# supply.net
KiCad netlist of a schematic drawn in Altium Designer
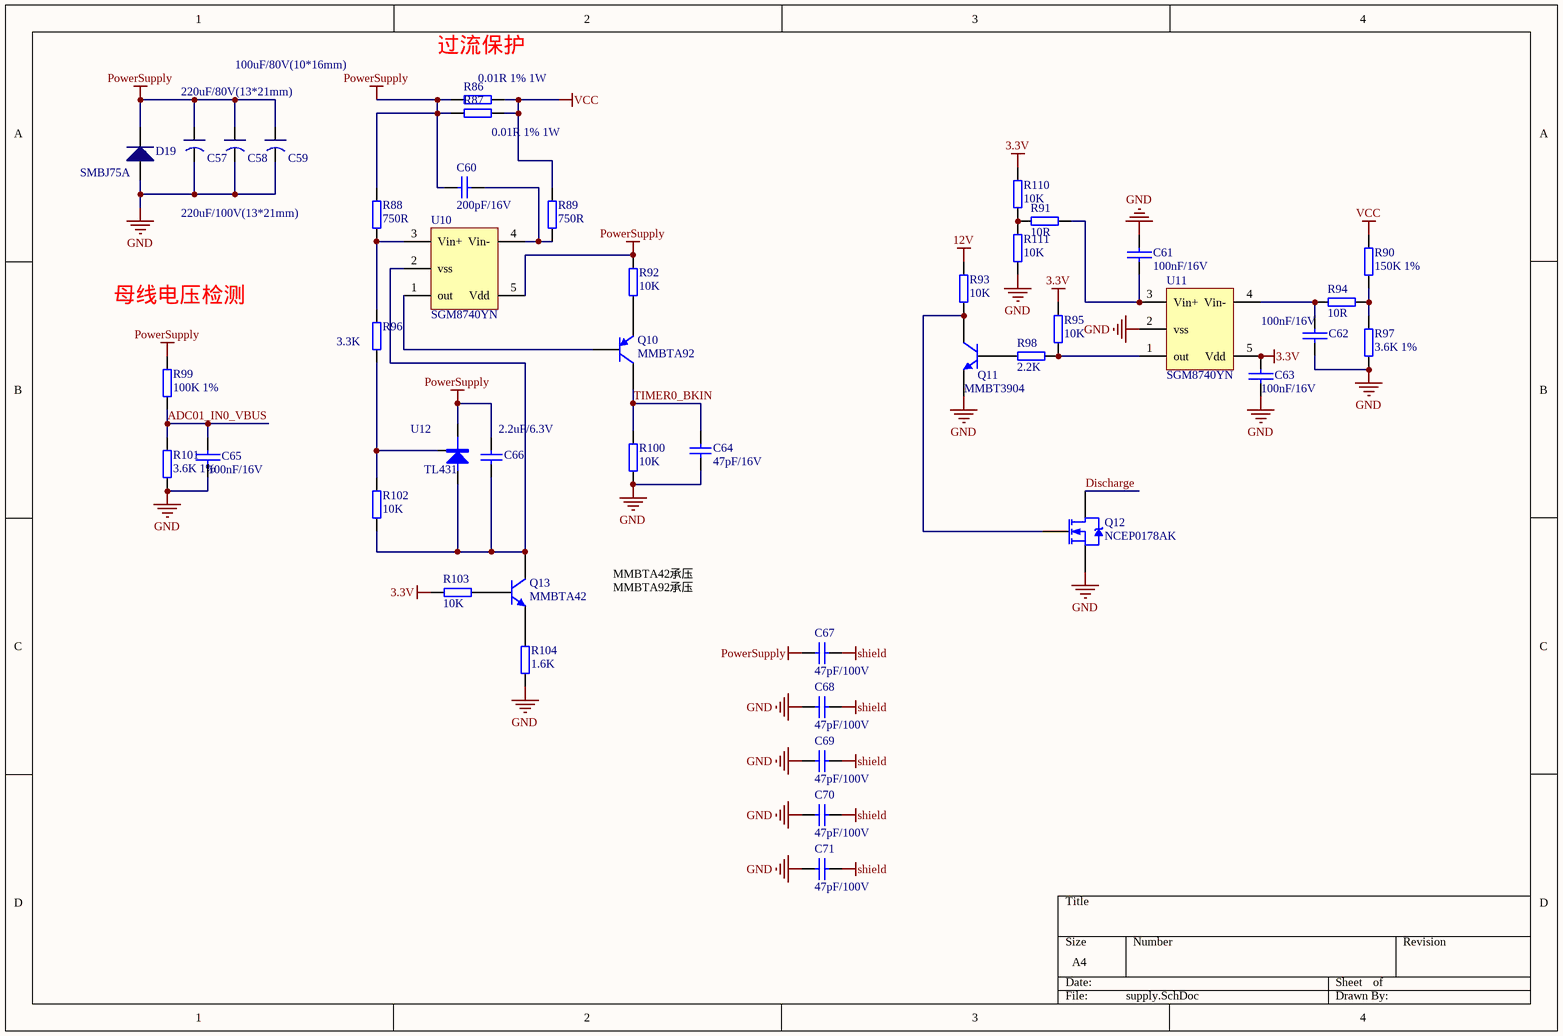
[diagram p0: supply.SchDoc]

(export (version "E")
  (design (tool "Eeschema 10.0.6"))
  (components
    (comp (ref "C57")
      (value "220uF/80V(13*21mm)")
      (footprint "AL-ELEC 13*21mm")
      (description "铝电解电容")
      (libsource (lib "Common Device") (part "Capacitor"))
    )
    (comp (ref "C58")
      (value "220uF/100V(13*21mm)")
      (footprint "AL-ELEC 13*21mm")
      (description "铝电解电容")
      (libsource (lib "Common Device") (part "Capacitor"))
    )
    (comp (ref "C59")
      (value "100uF/80V(10*16mm)")
      (footprint "AL-ELEC 10*16mm")
      (description "铝电解电容")
      (libsource (lib "Common Device") (part "Capacitor"))
    )
    (comp (ref "C60") (value "200pF/16V") (footprint "C0402") (libsource (lib "zijianku") (part "cap")))
    (comp (ref "C61")
      (value "100nF/16V")
      (footprint "C0402")
      (description "Capacitor")
      (libsource (lib "*") (part "CAP"))
    )
    (comp (ref "C62")
      (value "100nF/16V")
      (footprint "C0402")
      (description "Capacitor")
      (libsource (lib "*") (part "CAP"))
    )
    (comp (ref "C63")
      (value "100nF/16V")
      (footprint "C0402")
      (description "Capacitor")
      (libsource (lib "*") (part "CAP"))
    )
    (comp (ref "C64") (value "47pF/16V") (footprint "C0402") (libsource (lib "zijianku") (part "cap")))
    (comp (ref "C65")
      (value "100nF/16V")
      (footprint "C0402")
      (description "Capacitor")
      (libsource (lib "*") (part "CAP"))
    )
    (comp (ref "C66") (value "2.2uF/6.3V") (footprint "C0402") (libsource (lib "zijianku") (part "cap")))
    (comp (ref "C67") (value "47pF/100V") (footprint "C1206") (libsource (lib "zijianku") (part "cap")))
    (comp (ref "C68") (value "47pF/100V") (footprint "C1206") (libsource (lib "zijianku") (part "cap")))
    (comp (ref "C69") (value "47pF/100V") (footprint "C1206") (libsource (lib "zijianku") (part "cap")))
    (comp (ref "C70") (value "47pF/100V") (footprint "C1206") (libsource (lib "zijianku") (part "cap")))
    (comp (ref "C71") (value "47pF/100V") (footprint "C1206") (libsource (lib "zijianku") (part "cap")))
    (comp (ref "D19")
      (value "SMBJ75A")
      (footprint "DO-214AA SMB")
      (libsource (lib "Common Device") (part "Diode"))
    )
    (comp (ref "Q10") (value "MMBTA92") (footprint "SOT-23") (libsource (lib "zijianku") (part "PNP")))
    (comp (ref "Q11") (value "MMBT3904") (footprint "SOT-23") (libsource (lib "zijianku") (part "NPN")))
    (comp (ref "Q12")
      (value "NCEP0178AK")
      (footprint "D-PAK(TO-252AA)")
      (libsource (lib "zijianku") (part "N-channel Enhancement MOS"))
    )
    (comp (ref "Q13") (value "MMBTA42") (footprint "SOT-23") (libsource (lib "zijianku") (part "NPN")))
    (comp (ref "R86")
      (value "0.01R 1% 1W")
      (footprint "R1210")
      (libsource (lib "zijianku") (part "Resistance"))
    )
    (comp (ref "R87")
      (value "0.01R 1% 1W")
      (footprint "R1210")
      (libsource (lib "zijianku") (part "Resistance"))
    )
    (comp (ref "R88") (value "750R") (footprint "R0402") (libsource (lib "zijianku") (part "Resistance")))
    (comp (ref "R89") (value "750R") (footprint "R0402") (libsource (lib "zijianku") (part "Resistance")))
    (comp (ref "R90") (value "150K 1%") (footprint "R0603") (libsource (lib "zijianku") (part "Resistance")))
    (comp (ref "R91") (value "10R") (footprint "R0402") (libsource (lib "zijianku") (part "Resistance")))
    (comp (ref "R92") (value "10K") (footprint "R0402") (libsource (lib "zijianku") (part "Resistance")))
    (comp (ref "R93") (value "10K") (footprint "R0402") (libsource (lib "zijianku") (part "Resistance")))
    (comp (ref "R94") (value "10R") (footprint "R0402") (libsource (lib "zijianku") (part "Resistance")))
    (comp (ref "R95") (value "10K") (footprint "R0402") (libsource (lib "zijianku") (part "Resistance")))
    (comp (ref "R96") (value "3.3K") (footprint "R0402") (libsource (lib "zijianku") (part "Resistance")))
    (comp (ref "R97") (value "3.6K 1%") (footprint "R0603") (libsource (lib "zijianku") (part "Resistance")))
    (comp (ref "R98") (value "2.2K") (footprint "R0402") (libsource (lib "zijianku") (part "Resistance")))
    (comp (ref "R99") (value "100K 1%") (footprint "R0603") (libsource (lib "zijianku") (part "Resistance")))
    (comp (ref "R100") (value "10K") (footprint "R0402") (libsource (lib "zijianku") (part "Resistance")))
    (comp (ref "R101") (value "3.6K 1%") (footprint "R0603") (libsource (lib "zijianku") (part "Resistance")))
    (comp (ref "R102") (value "10K") (footprint "R0402") (libsource (lib "zijianku") (part "Resistance")))
    (comp (ref "R103") (value "10K") (footprint "R0402") (libsource (lib "zijianku") (part "Resistance")))
    (comp (ref "R104") (value "1.6K") (footprint "R0402") (libsource (lib "zijianku") (part "Resistance")))
    (comp (ref "R110") (value "10K") (footprint "R0402") (libsource (lib "zijianku") (part "Resistance")))
    (comp (ref "R111") (value "10K") (footprint "R0402") (libsource (lib "zijianku") (part "Resistance")))
    (comp (ref "U10")
      (value "SGM8740YN")
      (footprint "SOT-23(5)")
      (description "圣邦微电子 丝印 SL5XX")
      (libsource (lib "Common Device") (part "LMV7239"))
    )
    (comp (ref "U11")
      (value "SGM8740YN")
      (footprint "SOT-23(5)")
      (description "圣邦微电子 丝印 SL5XX")
      (libsource (lib "Common Device") (part "LMV7239"))
    )
    (comp (ref "U12")
      (value "TL431")
      (footprint "SOT-23")
      (description "注意引脚关系：1-C 2-R 3-A")
      (libsource (lib "zijianku") (part "TL431A"))
    )
  )
  (nets
    (net (code "1") (name "/ADC01_IN0_VBUS") (class "Default")
      (node (ref "C65") (pin "1") (pinfunction "1_1") (pintype "passive"))
      (node (ref "R101") (pin "2") (pintype "passive"))
      (node (ref "R99") (pin "1") (pintype "passive"))
    )
    (net (code "2") (name "/Discharge") (class "Default")
      (node (ref "Q12") (pin "3") (pinfunction "D_3") (pintype "passive"))
    )
    (net (code "3") (name "/TIMER0_BKIN") (class "Default")
      (node (ref "C64") (pin "1") (pinfunction "0_1") (pintype "passive"))
      (node (ref "Q10") (pin "3") (pinfunction "C_3") (pintype "passive"))
      (node (ref "R100") (pin "2") (pintype "passive"))
    )
    (net (code "4") (name "3.3V") (class "Default")
      (node (ref "C63") (pin "1") (pinfunction "1_1") (pintype "passive"))
      (node (ref "R103") (pin "1") (pintype "passive"))
      (node (ref "R110") (pin "2") (pintype "passive"))
      (node (ref "R95") (pin "2") (pintype "passive"))
      (node (ref "U11") (pin "5") (pinfunction "Vdd_5") (pintype "passive"))
    )
    (net (code "5") (name "12V") (class "Default") (node (ref "R93") (pin "2") (pintype "passive")))
    (net (code "6") (name "GND") (class "Default")
      (node (ref "C57") (pin "2") (pinfunction "1_2") (pintype "passive"))
      (node (ref "C58") (pin "2") (pinfunction "1_2") (pintype "passive"))
      (node (ref "C59") (pin "2") (pinfunction "1_2") (pintype "passive"))
      (node (ref "C61") (pin "2") (pinfunction "2_2") (pintype "passive"))
      (node (ref "C62") (pin "2") (pinfunction "2_2") (pintype "passive"))
      (node (ref "C63") (pin "2") (pinfunction "2_2") (pintype "passive"))
      (node (ref "C64") (pin "2") (pinfunction "1_2") (pintype "passive"))
      (node (ref "C65") (pin "2") (pinfunction "2_2") (pintype "passive"))
      (node (ref "C68") (pin "2") (pinfunction "1_2") (pintype "passive"))
      (node (ref "C69") (pin "2") (pinfunction "1_2") (pintype "passive"))
      (node (ref "C70") (pin "2") (pinfunction "1_2") (pintype "passive"))
      (node (ref "C71") (pin "2") (pinfunction "1_2") (pintype "passive"))
      (node (ref "D19") (pin "1") (pinfunction "0_1") (pintype "passive"))
      (node (ref "Q11") (pin "2") (pinfunction "E_2") (pintype "passive"))
      (node (ref "Q12") (pin "2") (pinfunction "S_2") (pintype "passive"))
      (node (ref "R100") (pin "1") (pintype "passive"))
      (node (ref "R101") (pin "1") (pintype "passive"))
      (node (ref "R104") (pin "1") (pintype "passive"))
      (node (ref "R111") (pin "1") (pintype "passive"))
      (node (ref "R97") (pin "1") (pintype "passive"))
      (node (ref "U11") (pin "2") (pinfunction "vss_2") (pintype "passive"))
    )
    (net (code "7") (name "Net-(C60-0)") (class "Default")
      (node (ref "C60") (pin "1") (pinfunction "0_1") (pintype "passive"))
      (node (ref "R89") (pin "1") (pintype "passive"))
      (node (ref "U10") (pin "4") (pinfunction "Vin-_4") (pintype "passive"))
    )
    (net (code "8") (name "Net-(C66-1)") (class "Default")
      (node (ref "C66") (pin "2") (pinfunction "1_2") (pintype "passive"))
      (node (ref "Q13") (pin "3") (pinfunction "C_3") (pintype "passive"))
      (node (ref "R102") (pin "2") (pintype "passive"))
      (node (ref "U10") (pin "2") (pinfunction "vss_2") (pintype "passive"))
      (node (ref "U12") (pin "3") (pinfunction "Anode_3") (pintype "passive"))
    )
    (net (code "9") (name "Net-(Q10-B)") (class "Default")
      (node (ref "Q10") (pin "1") (pinfunction "B_1") (pintype "passive"))
      (node (ref "U10") (pin "1") (pinfunction "out_1") (pintype "passive"))
    )
    (net (code "10") (name "Net-(Q10-E)") (class "Default")
      (node (ref "Q10") (pin "2") (pinfunction "E_2") (pintype "passive"))
      (node (ref "R92") (pin "1") (pintype "passive"))
    )
    (net (code "11") (name "Net-(Q11-B)") (class "Default")
      (node (ref "Q11") (pin "1") (pinfunction "B_1") (pintype "passive"))
      (node (ref "R98") (pin "1") (pintype "passive"))
    )
    (net (code "12") (name "Net-(Q11-C)") (class "Default")
      (node (ref "Q11") (pin "3") (pinfunction "C_3") (pintype "passive"))
      (node (ref "Q12") (pin "1") (pinfunction "G_1") (pintype "passive"))
      (node (ref "R93") (pin "1") (pintype "passive"))
    )
    (net (code "13") (name "Net-(Q13-B)") (class "Default")
      (node (ref "Q13") (pin "1") (pinfunction "B_1") (pintype "passive"))
      (node (ref "R103") (pin "2") (pintype "passive"))
    )
    (net (code "14") (name "Net-(Q13-E)") (class "Default")
      (node (ref "Q13") (pin "2") (pinfunction "E_2") (pintype "passive"))
      (node (ref "R104") (pin "2") (pintype "passive"))
    )
    (net (code "15") (name "Net-(R90-Pad1)") (class "Default")
      (node (ref "R90") (pin "1") (pintype "passive"))
      (node (ref "R94") (pin "1") (pintype "passive"))
      (node (ref "R97") (pin "2") (pintype "passive"))
    )
    (net (code "16") (name "Net-(R110-Pad1)") (class "Default")
      (node (ref "R110") (pin "1") (pintype "passive"))
      (node (ref "R111") (pin "2") (pintype "passive"))
      (node (ref "R91") (pin "2") (pintype "passive"))
    )
    (net (code "17") (name "Net-(U10-Vin+)") (class "Default")
      (node (ref "R88") (pin "1") (pintype "passive"))
      (node (ref "R96") (pin "1") (pintype "passive"))
      (node (ref "U10") (pin "3") (pinfunction "Vin+_3") (pintype "passive"))
    )
    (net (code "18") (name "Net-(U11-Vin+)") (class "Default")
      (node (ref "C61") (pin "1") (pinfunction "1_1") (pintype "passive"))
      (node (ref "R91") (pin "1") (pintype "passive"))
      (node (ref "U11") (pin "3") (pinfunction "Vin+_3") (pintype "passive"))
    )
    (net (code "19") (name "Net-(U11-Vin-)") (class "Default")
      (node (ref "C62") (pin "1") (pinfunction "1_1") (pintype "passive"))
      (node (ref "R94") (pin "2") (pintype "passive"))
      (node (ref "U11") (pin "4") (pinfunction "Vin-_4") (pintype "passive"))
    )
    (net (code "20") (name "Net-(U11-out)") (class "Default")
      (node (ref "R95") (pin "1") (pintype "passive"))
      (node (ref "R98") (pin "2") (pintype "passive"))
      (node (ref "U11") (pin "1") (pinfunction "out_1") (pintype "passive"))
    )
    (net (code "21") (name "Net-(U12-REF)") (class "Default")
      (node (ref "R102") (pin "1") (pintype "passive"))
      (node (ref "R96") (pin "2") (pintype "passive"))
      (node (ref "U12") (pin "2") (pinfunction "REF_2") (pintype "passive"))
    )
    (net (code "22") (name "PowerSupply") (class "Default")
      (node (ref "C57") (pin "1") (pinfunction "0_1") (pintype "passive"))
      (node (ref "C58") (pin "1") (pinfunction "0_1") (pintype "passive"))
      (node (ref "C59") (pin "1") (pinfunction "0_1") (pintype "passive"))
      (node (ref "C60") (pin "2") (pinfunction "1_2") (pintype "passive"))
      (node (ref "C66") (pin "1") (pinfunction "0_1") (pintype "passive"))
      (node (ref "C67") (pin "2") (pinfunction "1_2") (pintype "passive"))
      (node (ref "D19") (pin "2") (pinfunction "1_2") (pintype "passive"))
      (node (ref "R86") (pin "2") (pintype "passive"))
      (node (ref "R87") (pin "2") (pintype "passive"))
      (node (ref "R88") (pin "2") (pintype "passive"))
      (node (ref "R92") (pin "2") (pintype "passive"))
      (node (ref "R99") (pin "2") (pintype "passive"))
      (node (ref "U10") (pin "5") (pinfunction "Vdd_5") (pintype "passive"))
      (node (ref "U12") (pin "1") (pinfunction "Cathode_1") (pintype "passive"))
    )
    (net (code "23") (name "VCC") (class "Default")
      (node (ref "R86") (pin "1") (pintype "passive"))
      (node (ref "R87") (pin "1") (pintype "passive"))
      (node (ref "R89") (pin "2") (pintype "passive"))
      (node (ref "R90") (pin "2") (pintype "passive"))
    )
    (net (code "24") (name "shield") (class "Default")
      (node (ref "C67") (pin "1") (pinfunction "0_1") (pintype "passive"))
      (node (ref "C68") (pin "1") (pinfunction "0_1") (pintype "passive"))
      (node (ref "C69") (pin "1") (pinfunction "0_1") (pintype "passive"))
      (node (ref "C70") (pin "1") (pinfunction "0_1") (pintype "passive"))
      (node (ref "C71") (pin "1") (pinfunction "0_1") (pintype "passive"))
    )
  )
)
